# LEDs.net
KiCad netlist of a schematic drawn in Altium Designer
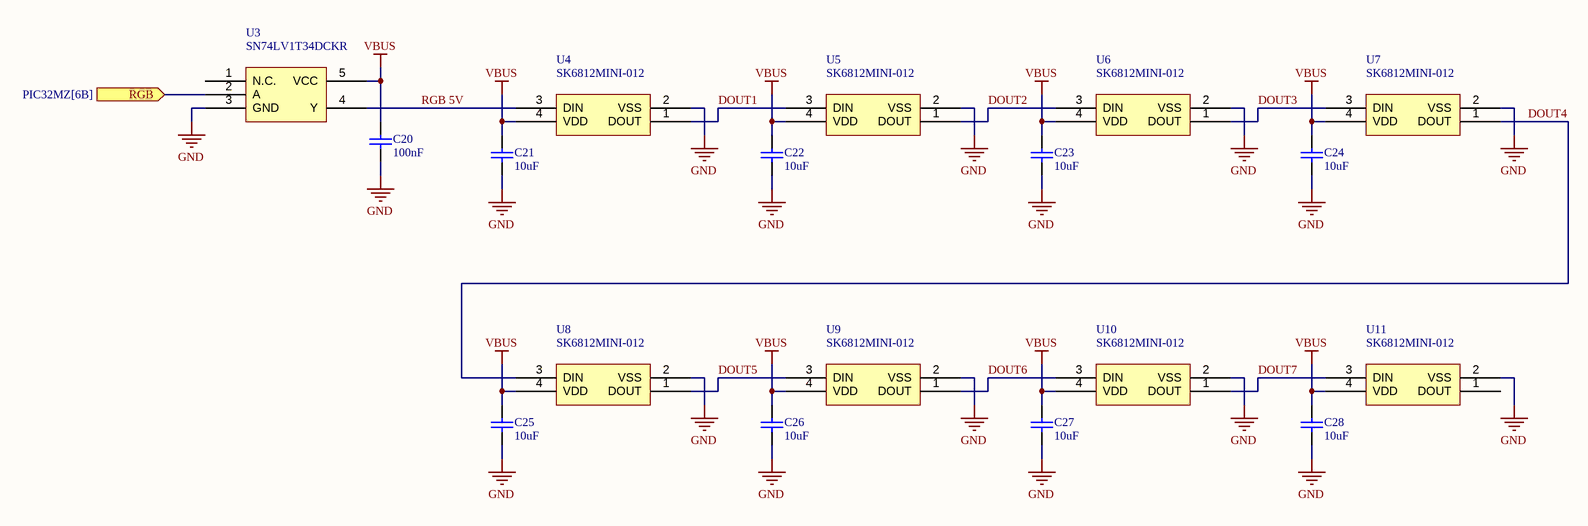
[diagram p0: LEDs.SchDoc]

(export (version "E")
  (design (tool "Eeschema 10.0.6"))
  (components
    (comp (ref "C20")
      (value "100nF")
      (footprint "Capacitor 0402")
      (libsource (lib "x-io") (part "Capacitor"))
    )
    (comp (ref "C21") (value "10uF") (footprint "Capacitor 0603") (libsource (lib "x-io") (part "Capacitor")))
    (comp (ref "C22") (value "10uF") (footprint "Capacitor 0603") (libsource (lib "x-io") (part "Capacitor")))
    (comp (ref "C23") (value "10uF") (footprint "Capacitor 0603") (libsource (lib "x-io") (part "Capacitor")))
    (comp (ref "C24") (value "10uF") (footprint "Capacitor 0603") (libsource (lib "x-io") (part "Capacitor")))
    (comp (ref "C25") (value "10uF") (footprint "Capacitor 0603") (libsource (lib "x-io") (part "Capacitor")))
    (comp (ref "C26") (value "10uF") (footprint "Capacitor 0603") (libsource (lib "x-io") (part "Capacitor")))
    (comp (ref "C27") (value "10uF") (footprint "Capacitor 0603") (libsource (lib "x-io") (part "Capacitor")))
    (comp (ref "C28") (value "10uF") (footprint "Capacitor 0603") (libsource (lib "x-io") (part "Capacitor")))
    (comp (ref "U3")
      (value "SN74LV1T34DCKR")
      (footprint "SOT-323-5")
      (libsource (lib "x-io") (part "SN74LVC1xxx (1 Input)"))
    )
    (comp (ref "U4")
      (value "SK6812MINI-012")
      (footprint "SK6812MINI-B-012")
      (libsource (lib "x-io") (part "SK6812MINI-B-012"))
    )
    (comp (ref "U5")
      (value "SK6812MINI-012")
      (footprint "SK6812MINI-B-012")
      (libsource (lib "x-io") (part "SK6812MINI-B-012"))
    )
    (comp (ref "U6")
      (value "SK6812MINI-012")
      (footprint "SK6812MINI-B-012")
      (libsource (lib "x-io") (part "SK6812MINI-B-012"))
    )
    (comp (ref "U7")
      (value "SK6812MINI-012")
      (footprint "SK6812MINI-B-012")
      (libsource (lib "x-io") (part "SK6812MINI-B-012"))
    )
    (comp (ref "U8")
      (value "SK6812MINI-012")
      (footprint "SK6812MINI-B-012")
      (libsource (lib "x-io") (part "SK6812MINI-B-012"))
    )
    (comp (ref "U9")
      (value "SK6812MINI-012")
      (footprint "SK6812MINI-B-012")
      (libsource (lib "x-io") (part "SK6812MINI-B-012"))
    )
    (comp (ref "U10")
      (value "SK6812MINI-012")
      (footprint "SK6812MINI-B-012")
      (libsource (lib "x-io") (part "SK6812MINI-B-012"))
    )
    (comp (ref "U11")
      (value "SK6812MINI-012")
      (footprint "SK6812MINI-B-012")
      (libsource (lib "x-io") (part "SK6812MINI-B-012"))
    )
  )
  (nets
    (net (code "1") (name "/DOUT1") (class "Default")
      (node (ref "U4") (pin "1") (pinfunction "DOUT_1") (pintype "passive"))
      (node (ref "U5") (pin "3") (pinfunction "DIN_3") (pintype "passive"))
    )
    (net (code "2") (name "/DOUT2") (class "Default")
      (node (ref "U5") (pin "1") (pinfunction "DOUT_1") (pintype "passive"))
      (node (ref "U6") (pin "3") (pinfunction "DIN_3") (pintype "passive"))
    )
    (net (code "3") (name "/DOUT3") (class "Default")
      (node (ref "U6") (pin "1") (pinfunction "DOUT_1") (pintype "passive"))
      (node (ref "U7") (pin "3") (pinfunction "DIN_3") (pintype "passive"))
    )
    (net (code "4") (name "/DOUT4") (class "Default")
      (node (ref "U7") (pin "1") (pinfunction "DOUT_1") (pintype "passive"))
      (node (ref "U8") (pin "3") (pinfunction "DIN_3") (pintype "passive"))
    )
    (net (code "5") (name "/DOUT5") (class "Default")
      (node (ref "U8") (pin "1") (pinfunction "DOUT_1") (pintype "passive"))
      (node (ref "U9") (pin "3") (pinfunction "DIN_3") (pintype "passive"))
    )
    (net (code "6") (name "/DOUT6") (class "Default")
      (node (ref "U10") (pin "3") (pinfunction "DIN_3") (pintype "passive"))
      (node (ref "U9") (pin "1") (pinfunction "DOUT_1") (pintype "passive"))
    )
    (net (code "7") (name "/DOUT7") (class "Default")
      (node (ref "U10") (pin "1") (pinfunction "DOUT_1") (pintype "passive"))
      (node (ref "U11") (pin "3") (pinfunction "DIN_3") (pintype "passive"))
    )
    (net (code "8") (name "/RGB") (class "Default")
      (node (ref "U3") (pin "2") (pinfunction "A_2") (pintype "passive"))
    )
    (net (code "9") (name "/RGB 5V") (class "Default")
      (node (ref "U3") (pin "4") (pinfunction "Y_4") (pintype "passive"))
      (node (ref "U4") (pin "3") (pinfunction "DIN_3") (pintype "passive"))
    )
    (net (code "10") (name "GND") (class "Default")
      (node (ref "C20") (pin "1") (pinfunction "1_1") (pintype "passive"))
      (node (ref "C21") (pin "1") (pinfunction "1_1") (pintype "passive"))
      (node (ref "C22") (pin "1") (pinfunction "1_1") (pintype "passive"))
      (node (ref "C23") (pin "1") (pinfunction "1_1") (pintype "passive"))
      (node (ref "C24") (pin "1") (pinfunction "1_1") (pintype "passive"))
      (node (ref "C25") (pin "1") (pinfunction "1_1") (pintype "passive"))
      (node (ref "C26") (pin "1") (pinfunction "1_1") (pintype "passive"))
      (node (ref "C27") (pin "1") (pinfunction "1_1") (pintype "passive"))
      (node (ref "C28") (pin "1") (pinfunction "1_1") (pintype "passive"))
      (node (ref "U10") (pin "2") (pinfunction "VSS_2") (pintype "passive"))
      (node (ref "U11") (pin "2") (pinfunction "VSS_2") (pintype "passive"))
      (node (ref "U3") (pin "3") (pinfunction "GND_3") (pintype "passive"))
      (node (ref "U4") (pin "2") (pinfunction "VSS_2") (pintype "passive"))
      (node (ref "U5") (pin "2") (pinfunction "VSS_2") (pintype "passive"))
      (node (ref "U6") (pin "2") (pinfunction "VSS_2") (pintype "passive"))
      (node (ref "U7") (pin "2") (pinfunction "VSS_2") (pintype "passive"))
      (node (ref "U8") (pin "2") (pinfunction "VSS_2") (pintype "passive"))
      (node (ref "U9") (pin "2") (pinfunction "VSS_2") (pintype "passive"))
    )
    (net (code "11") (name "VBUS") (class "Default")
      (node (ref "C20") (pin "2") (pinfunction "2_2") (pintype "passive"))
      (node (ref "C21") (pin "2") (pinfunction "2_2") (pintype "passive"))
      (node (ref "C22") (pin "2") (pinfunction "2_2") (pintype "passive"))
      (node (ref "C23") (pin "2") (pinfunction "2_2") (pintype "passive"))
      (node (ref "C24") (pin "2") (pinfunction "2_2") (pintype "passive"))
      (node (ref "C25") (pin "2") (pinfunction "2_2") (pintype "passive"))
      (node (ref "C26") (pin "2") (pinfunction "2_2") (pintype "passive"))
      (node (ref "C27") (pin "2") (pinfunction "2_2") (pintype "passive"))
      (node (ref "C28") (pin "2") (pinfunction "2_2") (pintype "passive"))
      (node (ref "U10") (pin "4") (pinfunction "VDD_4") (pintype "passive"))
      (node (ref "U11") (pin "4") (pinfunction "VDD_4") (pintype "passive"))
      (node (ref "U3") (pin "5") (pinfunction "VCC_5") (pintype "passive"))
      (node (ref "U4") (pin "4") (pinfunction "VDD_4") (pintype "passive"))
      (node (ref "U5") (pin "4") (pinfunction "VDD_4") (pintype "passive"))
      (node (ref "U6") (pin "4") (pinfunction "VDD_4") (pintype "passive"))
      (node (ref "U7") (pin "4") (pinfunction "VDD_4") (pintype "passive"))
      (node (ref "U8") (pin "4") (pinfunction "VDD_4") (pintype "passive"))
      (node (ref "U9") (pin "4") (pinfunction "VDD_4") (pintype "passive"))
    )
    (net (code "12") (name "unconnected-(U3-N.C.-Pad1)") (class "Default")
      (node (ref "U3") (pin "1") (pinfunction "N.C._1") (pintype "passive"))
    )
    (net (code "13") (name "unconnected-(U11-DOUT-Pad1)") (class "Default")
      (node (ref "U11") (pin "1") (pinfunction "DOUT_1") (pintype "passive"))
    )
  )
)
